# Aegaeon_REV_B_20130130_PROTO.net
KiCad netlist of a schematic drawn in EAGLE
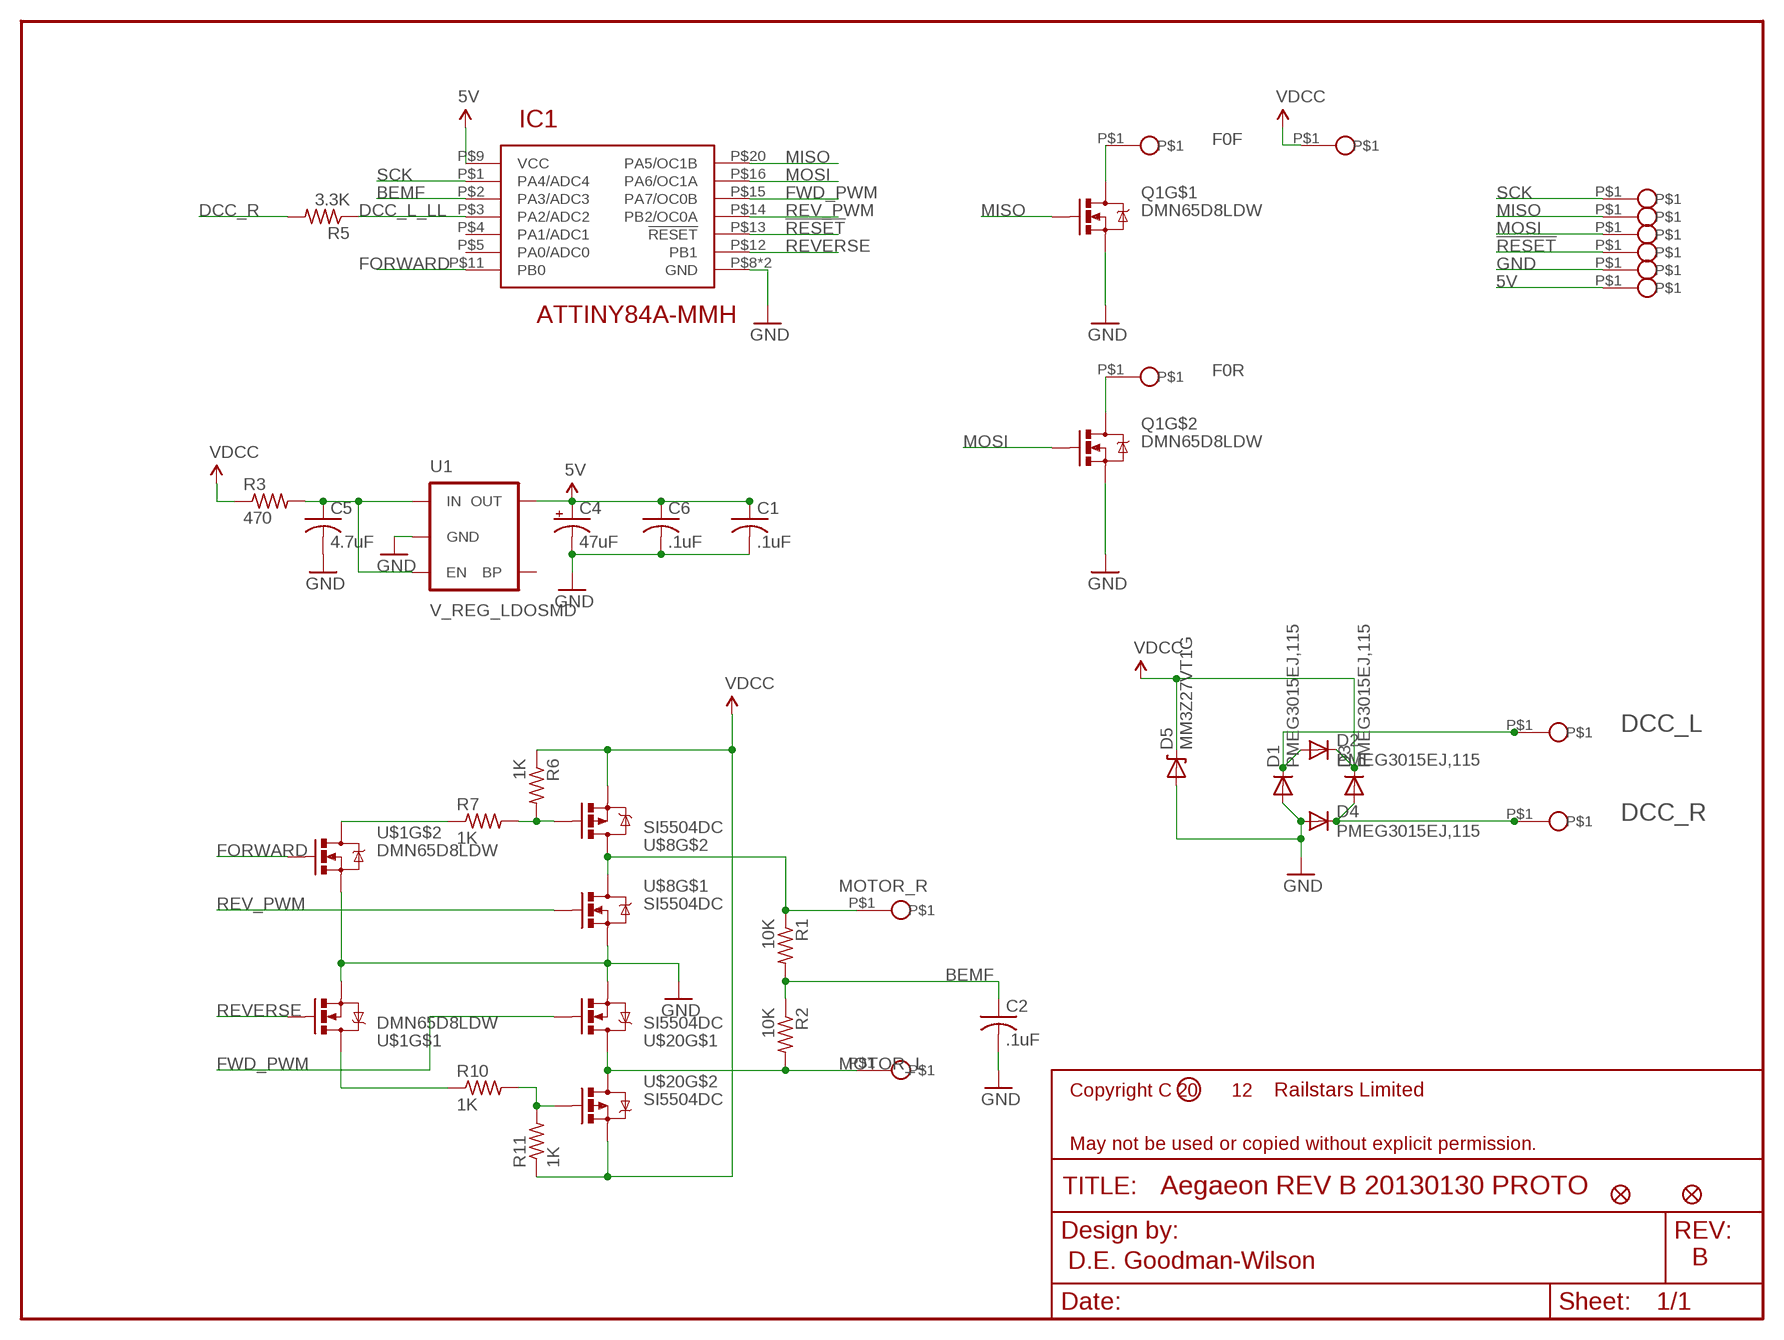
[diagram p0: schematic, sheet 1]

(export (version "E")
  (design (tool "Eeschema 10.0.6"))
  (components
    (comp (ref "C1")
      (value ".1uF")
      (footprint "eagle-import:C0201")
      (libsource (lib "eagle-import") (part "C-USC0201"))
    )
    (comp (ref "C2")
      (value ".1uF")
      (footprint "eagle-import:C0402")
      (libsource (lib "eagle-import") (part "C-USC0402"))
    )
    (comp (ref "C4")
      (value "47uF")
      (footprint "eagle-import:CPOL0603")
      (libsource (lib "eagle-import") (part "CPOL-USF980J476MMA"))
    )
    (comp (ref "C5")
      (value "4.7uF")
      (footprint "eagle-import:C0603")
      (libsource (lib "eagle-import") (part "C-USC0603"))
    )
    (comp (ref "C6")
      (value ".1uF")
      (footprint "eagle-import:C0402")
      (libsource (lib "eagle-import") (part "C-USC0402"))
    )
    (comp (ref "D1")
      (value "PMEG3015EJ,115")
      (footprint "eagle-import:SOD-323")
      (libsource (lib "eagle-import") (part "DIODESOD"))
    )
    (comp (ref "D2")
      (value "PMEG3015EJ,115")
      (footprint "eagle-import:SOD-323")
      (libsource (lib "eagle-import") (part "DIODESOD"))
    )
    (comp (ref "D3")
      (value "PMEG3015EJ,115")
      (footprint "eagle-import:SOD-323")
      (libsource (lib "eagle-import") (part "DIODESOD"))
    )
    (comp (ref "D4")
      (value "PMEG3015EJ,115")
      (footprint "eagle-import:SOD-323")
      (libsource (lib "eagle-import") (part "DIODESOD"))
    )
    (comp (ref "D5")
      (value "MM3Z27VT1G")
      (footprint "eagle-import:SOD-323")
      (libsource (lib "eagle-import") (part "DIODE-ZENER-BZT52"))
    )
    (comp (ref "DCC_L")
      (value "PAD1MM")
      (footprint "eagle-import:LED_SOLDER_PAD")
      (libsource (lib "eagle-import") (part "PAD1MM"))
    )
    (comp (ref "DCC_R")
      (value "PAD1MM")
      (footprint "eagle-import:LED_SOLDER_PAD")
      (libsource (lib "eagle-import") (part "PAD1MM"))
    )
    (comp (ref "IC1")
      (value "ATTINY84A-MMH")
      (footprint "eagle-import:VQFN-20")
      (libsource (lib "eagle-import") (part "ATTINY84A-MMH"))
    )
    (comp (ref "JP2")
      (value "FIDUCIALUFIDUCIAL")
      (footprint "eagle-import:MICRO-FIDUCIAL")
      (libsource (lib "eagle-import") (part "FIDUCIALUFIDUCIAL"))
    )
    (comp (ref "JP4")
      (value "FIDUCIALUFIDUCIAL")
      (footprint "eagle-import:MICRO-FIDUCIAL")
      (libsource (lib "eagle-import") (part "FIDUCIALUFIDUCIAL"))
    )
    (comp (ref "Q1")
      (value "DMN65D8LDW")
      (footprint "eagle-import:SOT363")
      (libsource (lib "eagle-import") (part "DMN65D8LDW"))
    )
    (comp (ref "R1")
      (value "10K")
      (footprint "eagle-import:R0201")
      (libsource (lib "eagle-import") (part "R-US_R0201"))
    )
    (comp (ref "R2")
      (value "10K")
      (footprint "eagle-import:R0201")
      (libsource (lib "eagle-import") (part "R-US_R0201"))
    )
    (comp (ref "R3")
      (value "470")
      (footprint "eagle-import:R0201")
      (libsource (lib "eagle-import") (part "R-US_R0201"))
    )
    (comp (ref "R5")
      (value "3.3K")
      (footprint "eagle-import:R0201")
      (libsource (lib "eagle-import") (part "R-US_R0201"))
    )
    (comp (ref "R6")
      (value "1K")
      (footprint "eagle-import:R0201")
      (libsource (lib "eagle-import") (part "R-US_R0201"))
    )
    (comp (ref "R7")
      (value "1K")
      (footprint "eagle-import:R0201")
      (libsource (lib "eagle-import") (part "R-US_R0201"))
    )
    (comp (ref "R10")
      (value "1K")
      (footprint "eagle-import:R0201")
      (libsource (lib "eagle-import") (part "R-US_R0201"))
    )
    (comp (ref "R11")
      (value "1K")
      (footprint "eagle-import:R0201")
      (libsource (lib "eagle-import") (part "R-US_R0201"))
    )
    (comp (ref "U$1")
      (value "DMN65D8LDW")
      (footprint "eagle-import:SOT363")
      (libsource (lib "eagle-import") (part "DMN65D8LDW"))
    )
    (comp (ref "U$2")
      (value "PAD1MM")
      (footprint "eagle-import:LED_SOLDER_PAD")
      (libsource (lib "eagle-import") (part "PAD1MM"))
    )
    (comp (ref "U$3")
      (value "PAD1MM")
      (footprint "eagle-import:LED_SOLDER_PAD")
      (libsource (lib "eagle-import") (part "PAD1MM"))
    )
    (comp (ref "U$5")
      (value "PAD1MM")
      (footprint "eagle-import:LED_SOLDER_PAD")
      (libsource (lib "eagle-import") (part "PAD1MM"))
    )
    (comp (ref "U$8")
      (value "SI5504DC")
      (footprint "eagle-import:1206-8")
      (libsource (lib "eagle-import") (part "SI5504DC"))
    )
    (comp (ref "U$10")
      (value "PAD1MM")
      (footprint "eagle-import:LED_SOLDER_PAD")
      (libsource (lib "eagle-import") (part "PAD1MM"))
    )
    (comp (ref "U$11")
      (value "PAD1MM")
      (footprint "eagle-import:LED_SOLDER_PAD")
      (libsource (lib "eagle-import") (part "PAD1MM"))
    )
    (comp (ref "U$14")
      (value "PAD.75MM")
      (footprint "eagle-import:POGO_PAD")
      (libsource (lib "eagle-import") (part "PAD.75MM"))
    )
    (comp (ref "U$15")
      (value "PAD.75MM")
      (footprint "eagle-import:POGO_PAD")
      (libsource (lib "eagle-import") (part "PAD.75MM"))
    )
    (comp (ref "U$16")
      (value "PAD.75MM")
      (footprint "eagle-import:POGO_PAD")
      (libsource (lib "eagle-import") (part "PAD.75MM"))
    )
    (comp (ref "U$17")
      (value "PAD.75MM")
      (footprint "eagle-import:POGO_PAD")
      (libsource (lib "eagle-import") (part "PAD.75MM"))
    )
    (comp (ref "U$18")
      (value "PAD.75MM")
      (footprint "eagle-import:POGO_PAD")
      (libsource (lib "eagle-import") (part "PAD.75MM"))
    )
    (comp (ref "U$19")
      (value "PAD.75MM")
      (footprint "eagle-import:POGO_PAD")
      (libsource (lib "eagle-import") (part "PAD.75MM"))
    )
    (comp (ref "U$20")
      (value "SI5504DC")
      (footprint "eagle-import:1206-8")
      (libsource (lib "eagle-import") (part "SI5504DC"))
    )
    (comp (ref "U1")
      (value "V_REG_LDOSMD")
      (footprint "eagle-import:SOT23-5")
      (libsource (lib "eagle-import") (part "V_REG_LDOSMD"))
    )
  )
  (nets
    (net (code "1") (name "/BEMF") (class "Default")
      (node (ref "C2") (pin "1") (pinfunction "1_1") (pintype "passive"))
      (node (ref "IC1") (pin "P$2") (pinfunction "PA3/ADC3_P$2") (pintype "bidirectional"))
      (node (ref "R1") (pin "2") (pinfunction "2_2") (pintype "passive"))
      (node (ref "R2") (pin "1") (pinfunction "1_1") (pintype "passive"))
    )
    (net (code "2") (name "/DCC_L") (class "Default")
      (node (ref "D1") (pin "1") (pinfunction "C_1") (pintype "passive"))
      (node (ref "D2") (pin "2") (pinfunction "A_2") (pintype "passive"))
      (node (ref "DCC_L") (pin "P$1") (pinfunction "P$1_P$1") (pintype "bidirectional"))
    )
    (net (code "3") (name "/DCC_L_LL") (class "Default")
      (node (ref "IC1") (pin "P$3") (pinfunction "PA2/ADC2_P$3") (pintype "bidirectional"))
      (node (ref "R5") (pin "1") (pinfunction "1_1") (pintype "passive"))
    )
    (net (code "4") (name "/DCC_R") (class "Default")
      (node (ref "D3") (pin "2") (pinfunction "A_2") (pintype "passive"))
      (node (ref "D4") (pin "1") (pinfunction "C_1") (pintype "passive"))
      (node (ref "DCC_R") (pin "P$1") (pinfunction "P$1_P$1") (pintype "bidirectional"))
      (node (ref "R5") (pin "2") (pinfunction "2_2") (pintype "passive"))
    )
    (net (code "5") (name "/F0F") (class "Default")
      (node (ref "Q1") (pin "P$4") (pinfunction "D_P$4") (pintype "passive"))
      (node (ref "U$10") (pin "P$1") (pinfunction "P$1_P$1") (pintype "bidirectional"))
    )
    (net (code "6") (name "/F0R") (class "Default")
      (node (ref "Q1") (pin "P$1") (pinfunction "D_P$1") (pintype "passive"))
      (node (ref "U$5") (pin "P$1") (pinfunction "P$1_P$1") (pintype "bidirectional"))
    )
    (net (code "7") (name "/FORWARD") (class "Default")
      (node (ref "IC1") (pin "P$11") (pinfunction "PB0_P$11") (pintype "bidirectional"))
      (node (ref "U$1") (pin "P$5") (pinfunction "G_P$5") (pintype "passive"))
    )
    (net (code "8") (name "/FWD_PWM") (class "Default")
      (node (ref "IC1") (pin "P$15") (pinfunction "PA7/OC0B_P$15") (pintype "bidirectional"))
      (node (ref "U$20") (pin "P$2") (pinfunction "G_P$2") (pintype "passive"))
    )
    (net (code "9") (name "/MISO") (class "Default")
      (node (ref "IC1") (pin "P$20") (pinfunction "PA5/OC1B_P$20") (pintype "bidirectional"))
      (node (ref "Q1") (pin "P$2") (pinfunction "G_P$2") (pintype "passive"))
      (node (ref "U$15") (pin "P$1") (pinfunction "P$1_P$1") (pintype "bidirectional"))
    )
    (net (code "10") (name "/MOSI") (class "Default")
      (node (ref "IC1") (pin "P$16") (pinfunction "PA6/OC1A_P$16") (pintype "bidirectional"))
      (node (ref "Q1") (pin "P$5") (pinfunction "G_P$5") (pintype "passive"))
      (node (ref "U$16") (pin "P$1") (pinfunction "P$1_P$1") (pintype "bidirectional"))
    )
    (net (code "11") (name "/MOTOR_L") (class "Default")
      (node (ref "R2") (pin "2") (pinfunction "2_2") (pintype "passive"))
      (node (ref "U$20") (pin "P$5") (pinfunction "D_P$5") (pintype "passive"))
      (node (ref "U$20") (pin "P$6") (pinfunction "D_P$6") (pintype "passive"))
      (node (ref "U$20") (pin "P$7") (pinfunction "D_P$7") (pintype "passive"))
      (node (ref "U$20") (pin "P$8") (pinfunction "D_P$8") (pintype "passive"))
      (node (ref "U$3") (pin "P$1") (pinfunction "P$1_P$1") (pintype "bidirectional"))
    )
    (net (code "12") (name "/MOTOR_R") (class "Default")
      (node (ref "R1") (pin "1") (pinfunction "1_1") (pintype "passive"))
      (node (ref "U$2") (pin "P$1") (pinfunction "P$1_P$1") (pintype "bidirectional"))
      (node (ref "U$8") (pin "P$5") (pinfunction "D_P$5") (pintype "passive"))
      (node (ref "U$8") (pin "P$6") (pinfunction "D_P$6") (pintype "passive"))
      (node (ref "U$8") (pin "P$7") (pinfunction "D_P$7") (pintype "passive"))
      (node (ref "U$8") (pin "P$8") (pinfunction "D_P$8") (pintype "passive"))
    )
    (net (code "13") (name "/REVERSE") (class "Default")
      (node (ref "IC1") (pin "P$12") (pinfunction "PB1_P$12") (pintype "bidirectional"))
      (node (ref "U$1") (pin "P$2") (pinfunction "G_P$2") (pintype "passive"))
    )
    (net (code "14") (name "/REV_PWM") (class "Default")
      (node (ref "IC1") (pin "P$14") (pinfunction "PB2/OC0A_P$14") (pintype "bidirectional"))
      (node (ref "U$8") (pin "P$2") (pinfunction "G_P$2") (pintype "passive"))
    )
    (net (code "15") (name "/SCK") (class "Default")
      (node (ref "IC1") (pin "P$1") (pinfunction "PA4/ADC4_P$1") (pintype "bidirectional"))
      (node (ref "U$14") (pin "P$1") (pinfunction "P$1_P$1") (pintype "bidirectional"))
    )
    (net (code "16") (name "/~{RESET}") (class "Default")
      (node (ref "IC1") (pin "P$13") (pinfunction "~{RESET}_P$13") (pintype "bidirectional"))
      (node (ref "U$17") (pin "P$1") (pinfunction "P$1_P$1") (pintype "bidirectional"))
    )
    (net (code "17") (name "5V") (class "Default")
      (node (ref "C1") (pin "1") (pinfunction "1_1") (pintype "passive"))
      (node (ref "C4") (pin "1") (pinfunction "+_1") (pintype "passive"))
      (node (ref "C6") (pin "1") (pinfunction "1_1") (pintype "passive"))
      (node (ref "IC1") (pin "P$9") (pinfunction "VCC_P$9") (pintype "bidirectional"))
      (node (ref "U$19") (pin "P$1") (pinfunction "P$1_P$1") (pintype "bidirectional"))
      (node (ref "U1") (pin "5") (pinfunction "OUT_5") (pintype "passive"))
    )
    (net (code "18") (name "GND") (class "Default")
      (node (ref "C1") (pin "2") (pinfunction "2_2") (pintype "passive"))
      (node (ref "C2") (pin "2") (pinfunction "2_2") (pintype "passive"))
      (node (ref "C4") (pin "2") (pinfunction "-_2") (pintype "passive"))
      (node (ref "C5") (pin "2") (pinfunction "2_2") (pintype "passive"))
      (node (ref "C6") (pin "2") (pinfunction "2_2") (pintype "passive"))
      (node (ref "D1") (pin "2") (pinfunction "A_2") (pintype "passive"))
      (node (ref "D4") (pin "2") (pinfunction "A_2") (pintype "passive"))
      (node (ref "D5") (pin "2") (pinfunction "A_2") (pintype "passive"))
      (node (ref "IC1") (pin "P$21") (pinfunction "GND_P$21") (pintype "bidirectional"))
      (node (ref "IC1") (pin "P$8") (pinfunction "GND_P$8") (pintype "bidirectional"))
      (node (ref "Q1") (pin "P$3") (pinfunction "S_P$3") (pintype "passive"))
      (node (ref "Q1") (pin "P$6") (pinfunction "S_P$6") (pintype "passive"))
      (node (ref "U$1") (pin "P$3") (pinfunction "S_P$3") (pintype "passive"))
      (node (ref "U$1") (pin "P$6") (pinfunction "S_P$6") (pintype "passive"))
      (node (ref "U$18") (pin "P$1") (pinfunction "P$1_P$1") (pintype "bidirectional"))
      (node (ref "U$20") (pin "P$1") (pinfunction "S_P$1") (pintype "passive"))
      (node (ref "U$8") (pin "P$1") (pinfunction "S_P$1") (pintype "passive"))
      (node (ref "U1") (pin "2") (pinfunction "GND_2") (pintype "input"))
    )
    (net (code "19") (name "Net-(U$1A-D)") (class "Default")
      (node (ref "R10") (pin "1") (pinfunction "1_1") (pintype "passive"))
      (node (ref "U$1") (pin "P$4") (pinfunction "D_P$4") (pintype "passive"))
    )
    (net (code "20") (name "Net-(U$1B-D)") (class "Default")
      (node (ref "R7") (pin "1") (pinfunction "1_1") (pintype "passive"))
      (node (ref "U$1") (pin "P$1") (pinfunction "D_P$1") (pintype "passive"))
    )
    (net (code "21") (name "Net-(U$8B-G)") (class "Default")
      (node (ref "R6") (pin "2") (pinfunction "2_2") (pintype "passive"))
      (node (ref "R7") (pin "2") (pinfunction "2_2") (pintype "passive"))
      (node (ref "U$8") (pin "P$4") (pinfunction "G_P$4") (pintype "passive"))
    )
    (net (code "22") (name "Net-(U$20B-G)") (class "Default")
      (node (ref "R10") (pin "2") (pinfunction "2_2") (pintype "passive"))
      (node (ref "R11") (pin "2") (pinfunction "2_2") (pintype "passive"))
      (node (ref "U$20") (pin "P$4") (pinfunction "G_P$4") (pintype "passive"))
    )
    (net (code "23") (name "Net-(U1-EN)") (class "Default")
      (node (ref "C5") (pin "1") (pinfunction "1_1") (pintype "passive"))
      (node (ref "R3") (pin "2") (pinfunction "2_2") (pintype "passive"))
      (node (ref "U1") (pin "1") (pinfunction "IN_1") (pintype "input"))
      (node (ref "U1") (pin "3") (pinfunction "EN_3") (pintype "input"))
    )
    (net (code "24") (name "VDCC") (class "Default")
      (node (ref "D2") (pin "1") (pinfunction "C_1") (pintype "passive"))
      (node (ref "D3") (pin "1") (pinfunction "C_1") (pintype "passive"))
      (node (ref "D5") (pin "1") (pinfunction "C_1") (pintype "passive"))
      (node (ref "R11") (pin "1") (pinfunction "1_1") (pintype "passive"))
      (node (ref "R3") (pin "1") (pinfunction "1_1") (pintype "passive"))
      (node (ref "R6") (pin "1") (pinfunction "1_1") (pintype "passive"))
      (node (ref "U$11") (pin "P$1") (pinfunction "P$1_P$1") (pintype "bidirectional"))
      (node (ref "U$20") (pin "P$3") (pinfunction "S_P$3") (pintype "passive"))
      (node (ref "U$8") (pin "P$3") (pinfunction "S_P$3") (pintype "passive"))
    )
    (net (code "25") (name "unconnected-(IC1-PA0{slash}ADC0-PadP$5)") (class "Default")
      (node (ref "IC1") (pin "P$5") (pinfunction "PA0/ADC0_P$5") (pintype "bidirectional"))
    )
    (net (code "26") (name "unconnected-(IC1-PA1{slash}ADC1-PadP$4)") (class "Default")
      (node (ref "IC1") (pin "P$4") (pinfunction "PA1/ADC1_P$4") (pintype "bidirectional"))
    )
    (net (code "27") (name "unconnected-(U1-BP-Pad4)") (class "Default")
      (node (ref "U1") (pin "4") (pinfunction "BP_4") (pintype "input"))
    )
  )
)
